# foc.net
KiCad netlist of a schematic drawn in Altium Designer
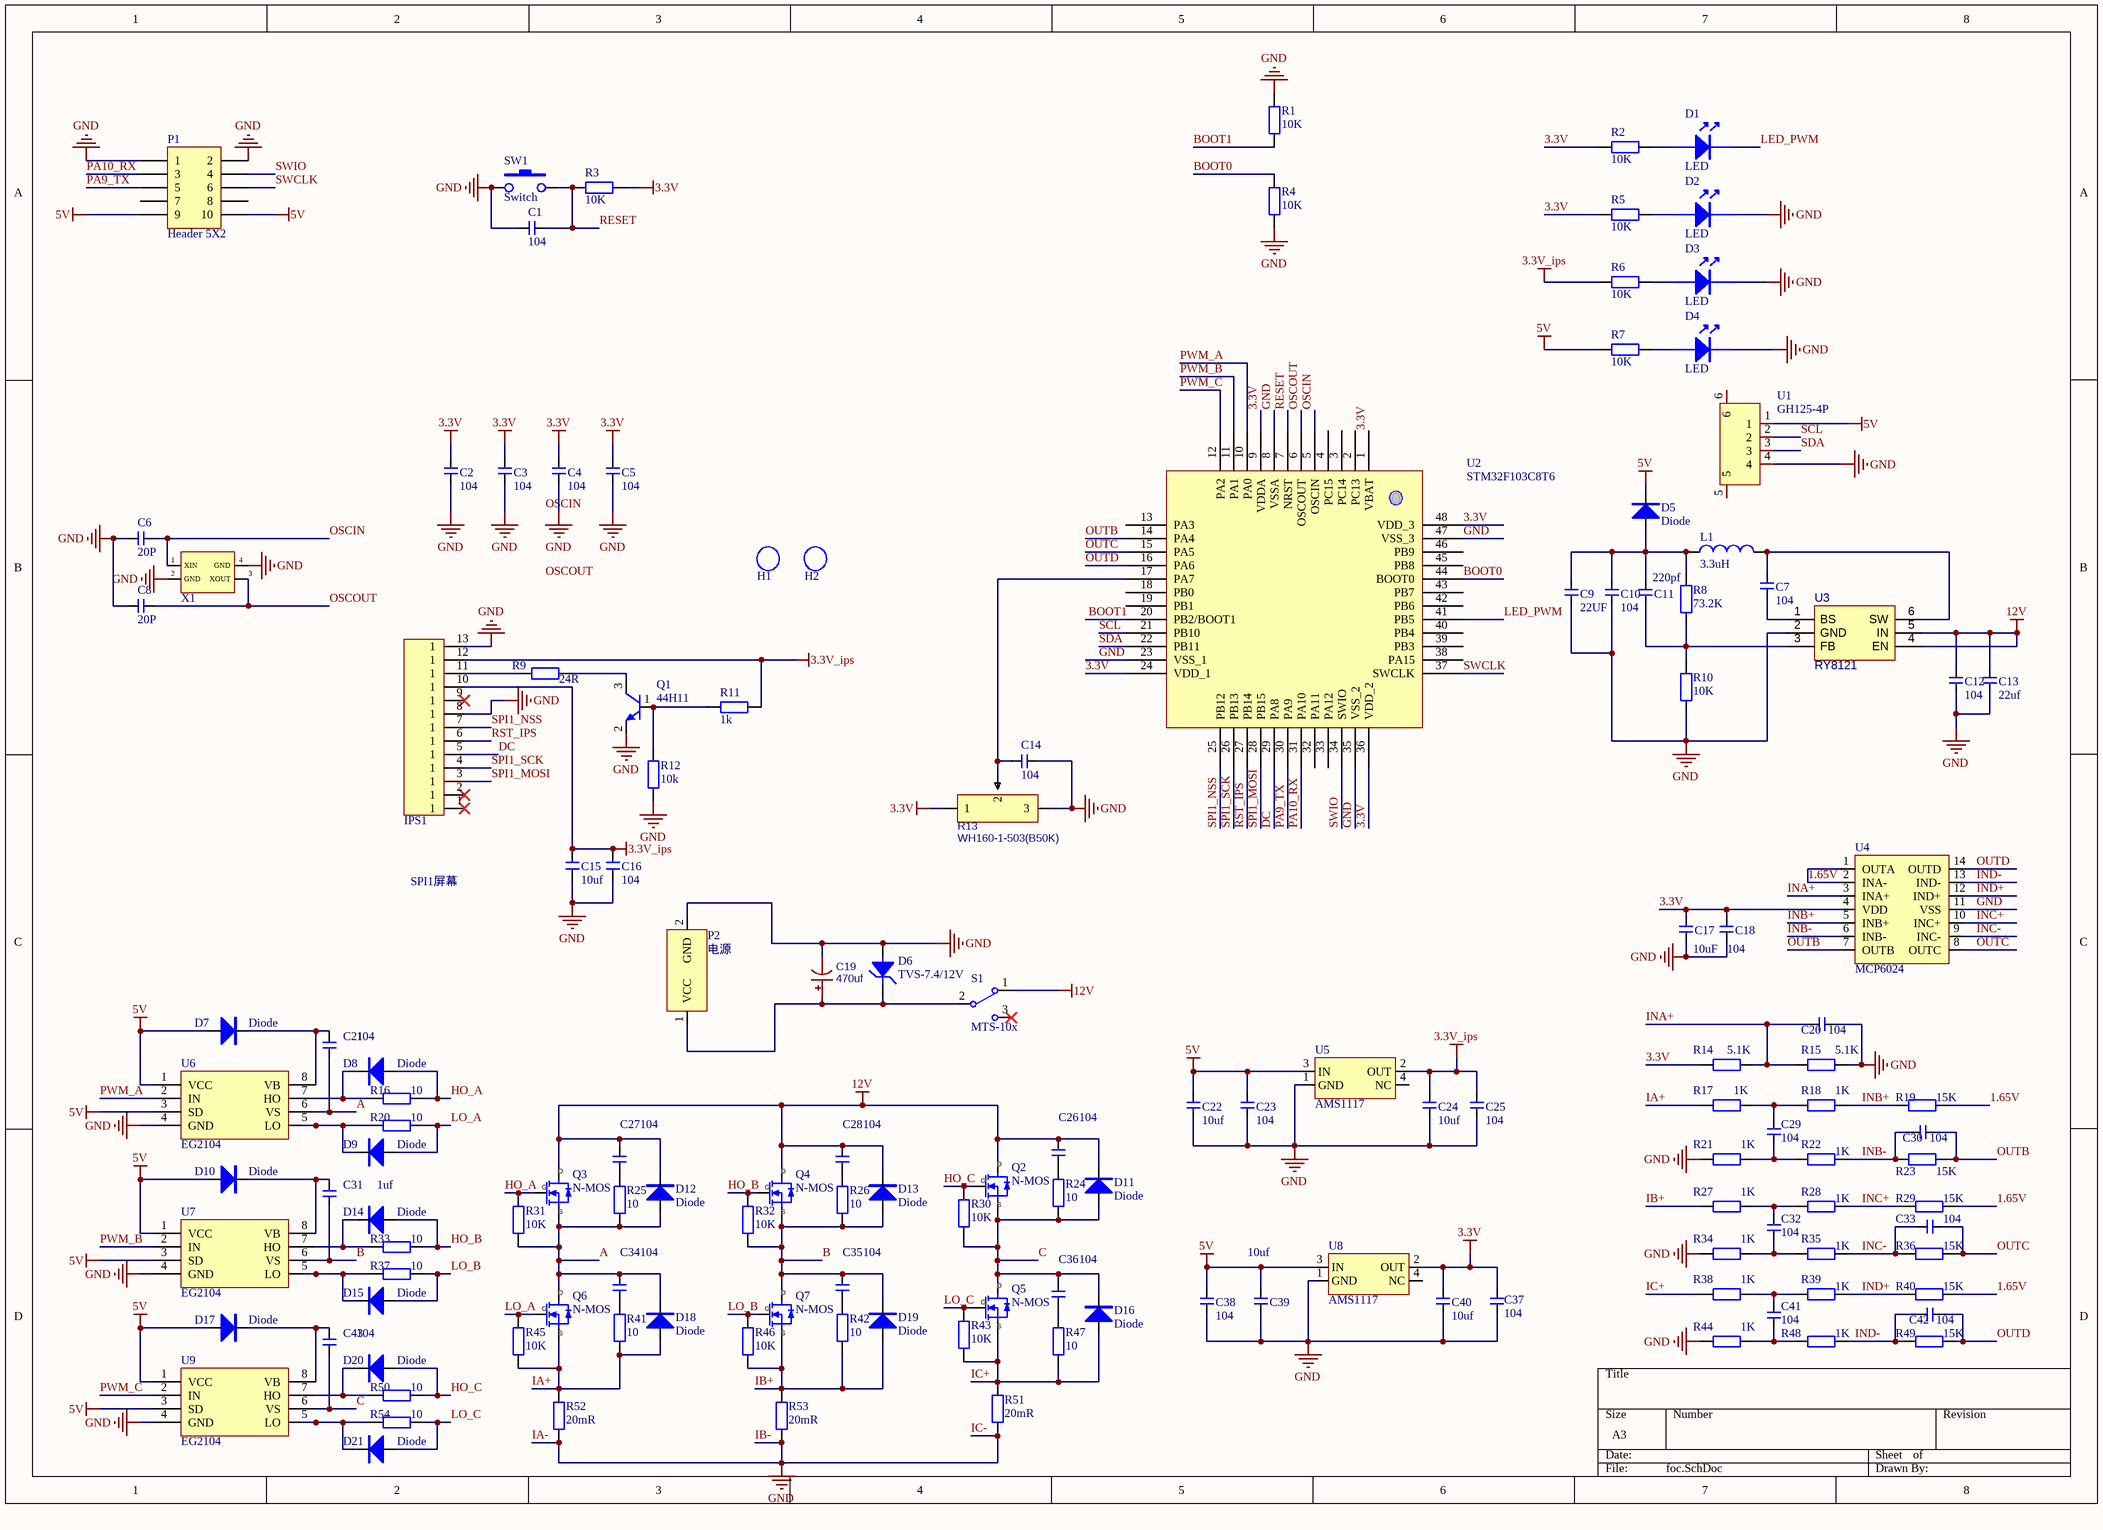
[diagram p0: foc.SchDoc]

(export (version "E")
  (design (tool "Eeschema 10.0.6"))
  (components
    (comp (ref "C1")
      (value "104")
      (footprint "C0603")
      (description "无极性电容")
      (fields (field (name "版权归属") "源创客"))
      (libsource (lib "鹏鹏总结的原理库") (part "C"))
    )
    (comp (ref "C2")
      (value "104")
      (footprint "C0603")
      (description "无极性电容")
      (fields (field (name "版权归属") "源创客"))
      (libsource (lib "鹏鹏总结的原理库") (part "C"))
    )
    (comp (ref "C3")
      (value "104")
      (footprint "C0603")
      (description "无极性电容")
      (fields (field (name "版权归属") "源创客"))
      (libsource (lib "鹏鹏总结的原理库") (part "C"))
    )
    (comp (ref "C4")
      (value "104")
      (footprint "C0603")
      (description "无极性电容")
      (fields (field (name "版权归属") "源创客"))
      (libsource (lib "鹏鹏总结的原理库") (part "C"))
    )
    (comp (ref "C5")
      (value "104")
      (footprint "C0603")
      (description "无极性电容")
      (fields (field (name "版权归属") "源创客"))
      (libsource (lib "鹏鹏总结的原理库") (part "C"))
    )
    (comp (ref "C6")
      (value "20P")
      (footprint "C0603")
      (description "无极性电容")
      (fields (field (name "版权归属") "源创客"))
      (libsource (lib "鹏鹏总结的原理库") (part "C"))
    )
    (comp (ref "C7")
      (value "104")
      (footprint "鹏鹏总结的pcb库:C0603")
      (description "无极性电容")
      (fields (field (name "版权归属") "源创客"))
      (libsource (lib "鹏鹏总结的原理库") (part "C"))
    )
    (comp (ref "C8")
      (value "20P")
      (footprint "C0603")
      (description "无极性电容")
      (fields (field (name "版权归属") "源创客"))
      (libsource (lib "鹏鹏总结的原理库") (part "C"))
    )
    (comp (ref "C9")
      (value "22UF")
      (footprint "鹏鹏总结的pcb库:C0603")
      (description "无极性电容")
      (fields (field (name "版权归属") "源创客"))
      (libsource (lib "鹏鹏总结的原理库") (part "C"))
    )
    (comp (ref "C10")
      (value "104")
      (footprint "鹏鹏总结的pcb库:C0603")
      (description "无极性电容")
      (fields (field (name "版权归属") "源创客"))
      (libsource (lib "鹏鹏总结的原理库") (part "C"))
    )
    (comp (ref "C11")
      (value "220pf")
      (footprint "鹏鹏总结的pcb库:C0603")
      (description "无极性电容")
      (fields (field (name "版权归属") "源创客"))
      (libsource (lib "鹏鹏总结的原理库") (part "C"))
    )
    (comp (ref "C12")
      (value "104")
      (footprint "鹏鹏总结的pcb库:C0603")
      (description "无极性电容")
      (fields (field (name "版权归属") "源创客"))
      (libsource (lib "鹏鹏总结的原理库") (part "C"))
    )
    (comp (ref "C13")
      (value "22uf")
      (footprint "鹏鹏总结的pcb库:C0603")
      (description "无极性电容")
      (fields (field (name "版权归属") "源创客"))
      (libsource (lib "鹏鹏总结的原理库") (part "C"))
    )
    (comp (ref "C14")
      (value "104")
      (footprint "C0603")
      (description "无极性电容")
      (fields (field (name "版权归属") "源创客"))
      (libsource (lib "鹏鹏总结的原理库") (part "C"))
    )
    (comp (ref "C15")
      (value "10uf")
      (footprint "鹏鹏总结的pcb库:C0603")
      (description "无极性电容")
      (fields (field (name "版权归属") "源创客"))
      (libsource (lib "") (part "C_1"))
    )
    (comp (ref "C16")
      (value "104")
      (footprint "鹏鹏总结的pcb库:C0603")
      (description "无极性电容")
      (fields (field (name "版权归属") "源创客"))
      (libsource (lib "") (part "C_1"))
    )
    (comp (ref "C17")
      (value "10uF")
      (footprint "鹏鹏总结的pcb库:C0603")
      (description "无极性电容")
      (fields (field (name "版权归属") "源创客"))
      (libsource (lib "鹏鹏总结的原理库") (part "C"))
    )
    (comp (ref "C18")
      (value "104")
      (footprint "鹏鹏总结的pcb库:C0603")
      (description "无极性电容")
      (fields (field (name "版权归属") "源创客"))
      (libsource (lib "鹏鹏总结的原理库") (part "C"))
    )
    (comp (ref "C19")
      (value "470uf")
      (footprint "CAP-SMD_BD6.3-L6.6-W6.6-LS7.2-R-RD")
      (description "电解电容 10uf  贴片型 钽电容的正极是实物有线的一段")
      (fields
        (field (name "BOM_MANUFACTURER PART") "RVT1V100M0405")
        (field (name "BOM_SUPPLIER PART") "C72485")
      )
      (libsource (lib "鹏鹏总结的原理库") (part "CAP+"))
    )
    (comp (ref "C20")
      (value "104")
      (footprint "鹏鹏总结的pcb库:C0603")
      (description "无极性电容")
      (fields (field (name "版权归属") "源创客"))
      (libsource (lib "鹏鹏总结的原理库") (part "C"))
    )
    (comp (ref "C21")
      (value "104")
      (footprint "鹏鹏总结的pcb库:C0603")
      (description "无极性电容")
      (fields (field (name "版权归属") "源创客"))
      (libsource (lib "鹏鹏总结的原理库") (part "C"))
    )
    (comp (ref "C22")
      (value "10uf")
      (footprint "鹏鹏总结的pcb库:C0603")
      (description "无极性电容")
      (fields (field (name "版权归属") "源创客"))
      (libsource (lib "鹏鹏总结的原理库") (part "C"))
    )
    (comp (ref "C23")
      (value "104")
      (footprint "鹏鹏总结的pcb库:C0603")
      (description "无极性电容")
      (fields (field (name "版权归属") "源创客"))
      (libsource (lib "鹏鹏总结的原理库") (part "C"))
    )
    (comp (ref "C24")
      (value "10uf")
      (footprint "鹏鹏总结的pcb库:C0603")
      (description "无极性电容")
      (fields (field (name "版权归属") "源创客"))
      (libsource (lib "鹏鹏总结的原理库") (part "C"))
    )
    (comp (ref "C25")
      (value "104")
      (footprint "鹏鹏总结的pcb库:C0603")
      (description "无极性电容")
      (fields (field (name "版权归属") "源创客"))
      (libsource (lib "鹏鹏总结的原理库") (part "C"))
    )
    (comp (ref "C26")
      (value "104")
      (footprint "鹏鹏总结的pcb库:C0603")
      (description "无极性电容")
      (fields (field (name "版权归属") "源创客"))
      (libsource (lib "鹏鹏总结的原理库") (part "C"))
    )
    (comp (ref "C27")
      (value "104")
      (footprint "鹏鹏总结的pcb库:C0603")
      (description "无极性电容")
      (fields (field (name "版权归属") "源创客"))
      (libsource (lib "鹏鹏总结的原理库") (part "C"))
    )
    (comp (ref "C28")
      (value "104")
      (footprint "鹏鹏总结的pcb库:C0603")
      (description "无极性电容")
      (fields (field (name "版权归属") "源创客"))
      (libsource (lib "鹏鹏总结的原理库") (part "C"))
    )
    (comp (ref "C29")
      (value "104")
      (footprint "鹏鹏总结的pcb库:C0603")
      (description "无极性电容")
      (fields (field (name "版权归属") "源创客"))
      (libsource (lib "鹏鹏总结的原理库") (part "C"))
    )
    (comp (ref "C30")
      (value "104")
      (footprint "鹏鹏总结的pcb库:C0603")
      (description "无极性电容")
      (fields (field (name "版权归属") "源创客"))
      (libsource (lib "鹏鹏总结的原理库") (part "C"))
    )
    (comp (ref "C31")
      (value "1uf")
      (footprint "鹏鹏总结的pcb库:C0603")
      (description "无极性电容")
      (fields (field (name "版权归属") "源创客"))
      (libsource (lib "鹏鹏总结的原理库") (part "C"))
    )
    (comp (ref "C32")
      (value "104")
      (footprint "鹏鹏总结的pcb库:C0603")
      (description "无极性电容")
      (fields (field (name "版权归属") "源创客"))
      (libsource (lib "鹏鹏总结的原理库") (part "C"))
    )
    (comp (ref "C33")
      (value "104")
      (footprint "鹏鹏总结的pcb库:C0603")
      (description "无极性电容")
      (fields (field (name "版权归属") "源创客"))
      (libsource (lib "鹏鹏总结的原理库") (part "C"))
    )
    (comp (ref "C34")
      (value "104")
      (footprint "鹏鹏总结的pcb库:C0603")
      (description "无极性电容")
      (fields (field (name "版权归属") "源创客"))
      (libsource (lib "鹏鹏总结的原理库") (part "C"))
    )
    (comp (ref "C35")
      (value "104")
      (footprint "鹏鹏总结的pcb库:C0603")
      (description "无极性电容")
      (fields (field (name "版权归属") "源创客"))
      (libsource (lib "鹏鹏总结的原理库") (part "C"))
    )
    (comp (ref "C36")
      (value "104")
      (footprint "鹏鹏总结的pcb库:C0603")
      (description "无极性电容")
      (fields (field (name "版权归属") "源创客"))
      (libsource (lib "鹏鹏总结的原理库") (part "C"))
    )
    (comp (ref "C37")
      (value "104")
      (footprint "鹏鹏总结的pcb库:C0603")
      (description "无极性电容")
      (fields (field (name "版权归属") "源创客"))
      (libsource (lib "鹏鹏总结的原理库") (part "C"))
    )
    (comp (ref "C38")
      (value "104")
      (footprint "鹏鹏总结的pcb库:C0603")
      (description "无极性电容")
      (fields (field (name "版权归属") "源创客"))
      (libsource (lib "鹏鹏总结的原理库") (part "C"))
    )
    (comp (ref "C39")
      (value "10uf")
      (footprint "鹏鹏总结的pcb库:C0603")
      (description "无极性电容")
      (fields (field (name "版权归属") "源创客"))
      (libsource (lib "鹏鹏总结的原理库") (part "C"))
    )
    (comp (ref "C40")
      (value "10uf")
      (footprint "鹏鹏总结的pcb库:C0603")
      (description "无极性电容")
      (fields (field (name "版权归属") "源创客"))
      (libsource (lib "鹏鹏总结的原理库") (part "C"))
    )
    (comp (ref "C41")
      (value "104")
      (footprint "鹏鹏总结的pcb库:C0603")
      (description "无极性电容")
      (fields (field (name "版权归属") "源创客"))
      (libsource (lib "鹏鹏总结的原理库") (part "C"))
    )
    (comp (ref "C42")
      (value "104")
      (footprint "鹏鹏总结的pcb库:C0603")
      (description "无极性电容")
      (fields (field (name "版权归属") "源创客"))
      (libsource (lib "鹏鹏总结的原理库") (part "C"))
    )
    (comp (ref "C43")
      (value "104")
      (footprint "鹏鹏总结的pcb库:C0603")
      (description "无极性电容")
      (fields (field (name "版权归属") "源创客"))
      (libsource (lib "鹏鹏总结的原理库") (part "C"))
    )
    (comp (ref "D1") (value "LED") (footprint "LED0603") (libsource (lib "鹏鹏总结的原理库") (part "LED")))
    (comp (ref "D2") (value "LED") (footprint "LED0603") (libsource (lib "鹏鹏总结的原理库") (part "LED")))
    (comp (ref "D3") (value "LED") (footprint "LED0603") (libsource (lib "鹏鹏总结的原理库") (part "LED")))
    (comp (ref "D4") (value "LED") (footprint "LED0603") (libsource (lib "鹏鹏总结的原理库") (part "LED")))
    (comp (ref "D5")
      (value "Diode")
      (footprint "SOD-123FL_L2.7-W1.8-LS3.8-RD")
      (description "Diode 1N series")
      (libsource (lib "鹏鹏总结的原理库") (part "二极管"))
    )
    (comp (ref "D6")
      (value "TVS-7.4/12V")
      (footprint "鹏鹏总结的pcb库:SMA")
      (libsource (lib "鹏鹏总结的原理库") (part "TVS-7.4/12V"))
    )
    (comp (ref "D7")
      (value "Diode")
      (footprint "SOD-123FL_L2.7-W1.8-LS3.8-RD")
      (description "Diode 1N series")
      (libsource (lib "鹏鹏总结的原理库") (part "二极管"))
    )
    (comp (ref "D8")
      (value "Diode")
      (footprint "ESC_L1.2-W0.8-LS1.6-RD")
      (description "Diode 1N series")
      (libsource (lib "鹏鹏总结的原理库") (part "二极管"))
    )
    (comp (ref "D9")
      (value "Diode")
      (footprint "ESC_L1.2-W0.8-LS1.6-RD")
      (description "Diode 1N series")
      (libsource (lib "鹏鹏总结的原理库") (part "二极管"))
    )
    (comp (ref "D10")
      (value "Diode")
      (footprint "SOD-123FL_L2.7-W1.8-LS3.8-RD")
      (description "Diode 1N series")
      (libsource (lib "鹏鹏总结的原理库") (part "二极管"))
    )
    (comp (ref "D11")
      (value "Diode")
      (footprint "SOD-123FL_L2.7-W1.8-LS3.8-RD")
      (description "Diode 1N series")
      (libsource (lib "鹏鹏总结的原理库") (part "二极管"))
    )
    (comp (ref "D12")
      (value "Diode")
      (footprint "SOD-123FL_L2.7-W1.8-LS3.8-RD")
      (description "Diode 1N series")
      (libsource (lib "鹏鹏总结的原理库") (part "二极管"))
    )
    (comp (ref "D13")
      (value "Diode")
      (footprint "SOD-123FL_L2.7-W1.8-LS3.8-RD")
      (description "Diode 1N series")
      (libsource (lib "鹏鹏总结的原理库") (part "二极管"))
    )
    (comp (ref "D14")
      (value "Diode")
      (footprint "ESC_L1.2-W0.8-LS1.6-RD")
      (description "Diode 1N series")
      (libsource (lib "鹏鹏总结的原理库") (part "二极管"))
    )
    (comp (ref "D15")
      (value "Diode")
      (footprint "ESC_L1.2-W0.8-LS1.6-RD")
      (description "Diode 1N series")
      (libsource (lib "鹏鹏总结的原理库") (part "二极管"))
    )
    (comp (ref "D16")
      (value "Diode")
      (footprint "SOD-123FL_L2.7-W1.8-LS3.8-RD")
      (description "Diode 1N series")
      (libsource (lib "鹏鹏总结的原理库") (part "二极管"))
    )
    (comp (ref "D17")
      (value "Diode")
      (footprint "SOD-123FL_L2.7-W1.8-LS3.8-RD")
      (description "Diode 1N series")
      (libsource (lib "鹏鹏总结的原理库") (part "二极管"))
    )
    (comp (ref "D18")
      (value "Diode")
      (footprint "SOD-123FL_L2.7-W1.8-LS3.8-RD")
      (description "Diode 1N series")
      (libsource (lib "鹏鹏总结的原理库") (part "二极管"))
    )
    (comp (ref "D19")
      (value "Diode")
      (footprint "SOD-123FL_L2.7-W1.8-LS3.8-RD")
      (description "Diode 1N series")
      (libsource (lib "鹏鹏总结的原理库") (part "二极管"))
    )
    (comp (ref "D20")
      (value "Diode")
      (footprint "ESC_L1.2-W0.8-LS1.6-RD")
      (description "Diode 1N series")
      (libsource (lib "鹏鹏总结的原理库") (part "二极管"))
    )
    (comp (ref "D21")
      (value "Diode")
      (footprint "ESC_L1.2-W0.8-LS1.6-RD")
      (description "Diode 1N series")
      (libsource (lib "鹏鹏总结的原理库") (part "二极管"))
    )
    (comp (ref "H1")
      (value "Hole")
      (footprint "铜柱孔3")
      (description "电机的洞")
      (libsource (lib "鹏鹏总结的原理库") (part "Hole"))
    )
    (comp (ref "H2")
      (value "Hole")
      (footprint "铜柱孔3")
      (description "电机的洞")
      (libsource (lib "鹏鹏总结的原理库") (part "Hole"))
    )
    (comp (ref "IPS1") (value "IPS1.14") (footprint "IPS") (libsource (lib "鹏鹏总结的原理库") (part "IPS1.14")))
    (comp (ref "L1")
      (value "3.3uH")
      (footprint "0402 TPC 4*4*2")
      (description "电感")
      (fields (field (name "版权归属") "源创客"))
      (libsource (lib "鹏鹏总结的原理库") (part "L"))
    )
    (comp (ref "P1")
      (value "Header 5X2")
      (footprint "HDR2X5")
      (description "Header, 5-Pin, Dual row")
      (fields (field (name "PUBLISHER") "Altium Limited"))
      (libsource (lib "Miscellaneous Connectors") (part "Header 5X2"))
    )
    (comp (ref "P2") (value "电源") (footprint "POWER") (libsource (lib "鹏鹏总结的原理库") (part "power")))
    (comp (ref "Q1")
      (value "44H11")
      (footprint "SOT-23-3_L2.9-W1.3-P1.90-LS2.4-BR")
      (description "NPN型")
      (fields (field (name "版权归属") "源创客"))
      (libsource (lib "鹏鹏总结的原理库") (part "NPN"))
    )
    (comp (ref "Q2")
      (value "N-MOS")
      (footprint "TDSON-8")
      (description "N沟场效应管")
      (fields (field (name "版权归属") "源创客"))
      (libsource (lib "鹏鹏总结的原理库") (part "N-MOS"))
    )
    (comp (ref "Q3")
      (value "N-MOS")
      (footprint "TDSON-8")
      (description "N沟场效应管")
      (fields (field (name "版权归属") "源创客"))
      (libsource (lib "鹏鹏总结的原理库") (part "N-MOS"))
    )
    (comp (ref "Q4")
      (value "N-MOS")
      (footprint "TDSON-8")
      (description "N沟场效应管")
      (fields (field (name "版权归属") "源创客"))
      (libsource (lib "鹏鹏总结的原理库") (part "N-MOS"))
    )
    (comp (ref "Q5")
      (value "N-MOS")
      (footprint "TDSON-8")
      (description "N沟场效应管")
      (fields (field (name "版权归属") "源创客"))
      (libsource (lib "鹏鹏总结的原理库") (part "N-MOS"))
    )
    (comp (ref "Q6")
      (value "N-MOS")
      (footprint "TDSON-8")
      (description "N沟场效应管")
      (fields (field (name "版权归属") "源创客"))
      (libsource (lib "鹏鹏总结的原理库") (part "N-MOS"))
    )
    (comp (ref "Q7")
      (value "N-MOS")
      (footprint "TDSON-8")
      (description "N沟场效应管")
      (fields (field (name "版权归属") "源创客"))
      (libsource (lib "鹏鹏总结的原理库") (part "N-MOS"))
    )
    (comp (ref "R1")
      (value "10K")
      (footprint "鹏鹏总结的pcb库:R0603")
      (description "电阻")
      (fields (field (name "版权归属") "源创客"))
      (libsource (lib "鹏鹏总结的原理库") (part "R"))
    )
    (comp (ref "R2")
      (value "10K")
      (footprint "鹏鹏总结的pcb库:R0603")
      (description "电阻")
      (fields (field (name "版权归属") "源创客"))
      (libsource (lib "鹏鹏总结的原理库") (part "R"))
    )
    (comp (ref "R3")
      (value "10K")
      (footprint "鹏鹏总结的pcb库:R0603")
      (description "电阻")
      (fields (field (name "版权归属") "源创客"))
      (libsource (lib "鹏鹏总结的原理库") (part "R"))
    )
    (comp (ref "R4")
      (value "10K")
      (footprint "鹏鹏总结的pcb库:R0603")
      (description "电阻")
      (fields (field (name "版权归属") "源创客"))
      (libsource (lib "鹏鹏总结的原理库") (part "R"))
    )
    (comp (ref "R5")
      (value "10K")
      (footprint "鹏鹏总结的pcb库:R0603")
      (description "电阻")
      (fields (field (name "版权归属") "源创客"))
      (libsource (lib "鹏鹏总结的原理库") (part "R"))
    )
    (comp (ref "R6")
      (value "10K")
      (footprint "鹏鹏总结的pcb库:R0603")
      (description "电阻")
      (fields (field (name "版权归属") "源创客"))
      (libsource (lib "鹏鹏总结的原理库") (part "R"))
    )
    (comp (ref "R7")
      (value "10K")
      (footprint "鹏鹏总结的pcb库:R0603")
      (description "电阻")
      (fields (field (name "版权归属") "源创客"))
      (libsource (lib "鹏鹏总结的原理库") (part "R"))
    )
    (comp (ref "R8")
      (value "73.2K")
      (footprint "鹏鹏总结的pcb库:R0603")
      (description "电阻")
      (fields (field (name "版权归属") "源创客"))
      (libsource (lib "鹏鹏总结的原理库") (part "R"))
    )
    (comp (ref "R9")
      (value "24R")
      (footprint "鹏鹏总结的pcb库:R0603")
      (description "电阻")
      (fields (field (name "版权归属") "源创客"))
      (libsource (lib "鹏鹏总结的原理库") (part "R"))
    )
    (comp (ref "R10")
      (value "10K")
      (footprint "鹏鹏总结的pcb库:R0603")
      (description "电阻")
      (fields (field (name "版权归属") "源创客"))
      (libsource (lib "鹏鹏总结的原理库") (part "R"))
    )
    (comp (ref "R11")
      (value "1k")
      (footprint "鹏鹏总结的pcb库:R0603")
      (description "电阻")
      (fields (field (name "版权归属") "源创客"))
      (libsource (lib "鹏鹏总结的原理库") (part "R"))
    )
    (comp (ref "R12")
      (value "10k")
      (footprint "鹏鹏总结的pcb库:R0603")
      (description "电阻")
      (fields (field (name "版权归属") "源创客"))
      (libsource (lib "鹏鹏总结的原理库") (part "R"))
    )
    (comp (ref "R13")
      (value "WH160-1-503(B50K)")
      (footprint "滑动变阻器")
      (description "拨码开关")
      (fields (field (name "MANUFACTURER") "JML"))
      (libsource (lib "鹏鹏总结的原理库") (part "WH160-1-503(B50K)"))
    )
    (comp (ref "R14")
      (value "5.1K")
      (footprint "鹏鹏总结的pcb库:R0603")
      (description "电阻")
      (fields (field (name "版权归属") "源创客"))
      (libsource (lib "鹏鹏总结的原理库") (part "R"))
    )
    (comp (ref "R15")
      (value "5.1K")
      (footprint "鹏鹏总结的pcb库:R0603")
      (description "电阻")
      (fields (field (name "版权归属") "源创客"))
      (libsource (lib "鹏鹏总结的原理库") (part "R"))
    )
    (comp (ref "R16")
      (value "10")
      (footprint "鹏鹏总结的pcb库:R0603")
      (description "电阻")
      (fields (field (name "版权归属") "源创客"))
      (libsource (lib "鹏鹏总结的原理库") (part "R"))
    )
    (comp (ref "R17")
      (value "1K")
      (footprint "鹏鹏总结的pcb库:R0603")
      (description "电阻")
      (fields (field (name "版权归属") "源创客"))
      (libsource (lib "鹏鹏总结的原理库") (part "R"))
    )
    (comp (ref "R18")
      (value "1K")
      (footprint "鹏鹏总结的pcb库:R0603")
      (description "电阻")
      (fields (field (name "版权归属") "源创客"))
      (libsource (lib "鹏鹏总结的原理库") (part "R"))
    )
    (comp (ref "R19")
      (value "15K")
      (footprint "鹏鹏总结的pcb库:R0603")
      (description "电阻")
      (fields (field (name "版权归属") "源创客"))
      (libsource (lib "鹏鹏总结的原理库") (part "R"))
    )
    (comp (ref "R20")
      (value "10")
      (footprint "鹏鹏总结的pcb库:R0603")
      (description "电阻")
      (fields (field (name "版权归属") "源创客"))
      (libsource (lib "鹏鹏总结的原理库") (part "R"))
    )
    (comp (ref "R21")
      (value "1K")
      (footprint "鹏鹏总结的pcb库:R0603")
      (description "电阻")
      (fields (field (name "版权归属") "源创客"))
      (libsource (lib "鹏鹏总结的原理库") (part "R"))
    )
    (comp (ref "R22")
      (value "1K")
      (footprint "鹏鹏总结的pcb库:R0603")
      (description "电阻")
      (fields (field (name "版权归属") "源创客"))
      (libsource (lib "鹏鹏总结的原理库") (part "R"))
    )
    (comp (ref "R23")
      (value "15K")
      (footprint "鹏鹏总结的pcb库:R0603")
      (description "电阻")
      (fields (field (name "版权归属") "源创客"))
      (libsource (lib "鹏鹏总结的原理库") (part "R"))
    )
    (comp (ref "R24")
      (value "10")
      (footprint "鹏鹏总结的pcb库:R0603")
      (description "电阻")
      (fields (field (name "版权归属") "源创客"))
      (libsource (lib "鹏鹏总结的原理库") (part "R"))
    )
    (comp (ref "R25")
      (value "10")
      (footprint "鹏鹏总结的pcb库:R0603")
      (description "电阻")
      (fields (field (name "版权归属") "源创客"))
      (libsource (lib "鹏鹏总结的原理库") (part "R"))
    )
    (comp (ref "R26")
      (value "10")
      (footprint "鹏鹏总结的pcb库:R0603")
      (description "电阻")
      (fields (field (name "版权归属") "源创客"))
      (libsource (lib "鹏鹏总结的原理库") (part "R"))
    )
    (comp (ref "R27")
      (value "1K")
      (footprint "鹏鹏总结的pcb库:R0603")
      (description "电阻")
      (fields (field (name "版权归属") "源创客"))
      (libsource (lib "鹏鹏总结的原理库") (part "R"))
    )
    (comp (ref "R28")
      (value "1K")
      (footprint "鹏鹏总结的pcb库:R0603")
      (description "电阻")
      (fields (field (name "版权归属") "源创客"))
      (libsource (lib "鹏鹏总结的原理库") (part "R"))
    )
    (comp (ref "R29")
      (value "15K")
      (footprint "鹏鹏总结的pcb库:R0603")
      (description "电阻")
      (fields (field (name "版权归属") "源创客"))
      (libsource (lib "鹏鹏总结的原理库") (part "R"))
    )
    (comp (ref "R30")
      (value "10K")
      (footprint "鹏鹏总结的pcb库:R0603")
      (description "电阻")
      (fields (field (name "版权归属") "源创客"))
      (libsource (lib "鹏鹏总结的原理库") (part "R"))
    )
    (comp (ref "R31")
      (value "10K")
      (footprint "鹏鹏总结的pcb库:R0603")
      (description "电阻")
      (fields (field (name "版权归属") "源创客"))
      (libsource (lib "鹏鹏总结的原理库") (part "R"))
    )
    (comp (ref "R32")
      (value "10K")
      (footprint "鹏鹏总结的pcb库:R0603")
      (description "电阻")
      (fields (field (name "版权归属") "源创客"))
      (libsource (lib "鹏鹏总结的原理库") (part "R"))
    )
    (comp (ref "R33")
      (value "10")
      (footprint "鹏鹏总结的pcb库:R0603")
      (description "电阻")
      (fields (field (name "版权归属") "源创客"))
      (libsource (lib "鹏鹏总结的原理库") (part "R"))
    )
    (comp (ref "R34")
      (value "1K")
      (footprint "鹏鹏总结的pcb库:R0603")
      (description "电阻")
      (fields (field (name "版权归属") "源创客"))
      (libsource (lib "鹏鹏总结的原理库") (part "R"))
    )
    (comp (ref "R35")
      (value "1K")
      (footprint "鹏鹏总结的pcb库:R0603")
      (description "电阻")
      (fields (field (name "版权归属") "源创客"))
      (libsource (lib "鹏鹏总结的原理库") (part "R"))
    )
    (comp (ref "R36")
      (value "15K")
      (footprint "鹏鹏总结的pcb库:R0603")
      (description "电阻")
      (fields (field (name "版权归属") "源创客"))
      (libsource (lib "鹏鹏总结的原理库") (part "R"))
    )
    (comp (ref "R37")
      (value "10")
      (footprint "鹏鹏总结的pcb库:R0603")
      (description "电阻")
      (fields (field (name "版权归属") "源创客"))
      (libsource (lib "鹏鹏总结的原理库") (part "R"))
    )
    (comp (ref "R38")
      (value "1K")
      (footprint "鹏鹏总结的pcb库:R0603")
      (description "电阻")
      (fields (field (name "版权归属") "源创客"))
      (libsource (lib "鹏鹏总结的原理库") (part "R"))
    )
    (comp (ref "R39")
      (value "1K")
      (footprint "鹏鹏总结的pcb库:R0603")
      (description "电阻")
      (fields (field (name "版权归属") "源创客"))
      (libsource (lib "鹏鹏总结的原理库") (part "R"))
    )
    (comp (ref "R40")
      (value "15K")
      (footprint "鹏鹏总结的pcb库:R0603")
      (description "电阻")
      (fields (field (name "版权归属") "源创客"))
      (libsource (lib "鹏鹏总结的原理库") (part "R"))
    )
    (comp (ref "R41")
      (value "10")
      (footprint "鹏鹏总结的pcb库:R0603")
      (description "电阻")
      (fields (field (name "版权归属") "源创客"))
      (libsource (lib "鹏鹏总结的原理库") (part "R"))
    )
    (comp (ref "R42")
      (value "10")
      (footprint "鹏鹏总结的pcb库:R0603")
      (description "电阻")
      (fields (field (name "版权归属") "源创客"))
      (libsource (lib "鹏鹏总结的原理库") (part "R"))
    )
    (comp (ref "R43")
      (value "10K")
      (footprint "鹏鹏总结的pcb库:R0603")
      (description "电阻")
      (fields (field (name "版权归属") "源创客"))
      (libsource (lib "鹏鹏总结的原理库") (part "R"))
    )
    (comp (ref "R44")
      (value "1K")
      (footprint "鹏鹏总结的pcb库:R0603")
      (description "电阻")
      (fields (field (name "版权归属") "源创客"))
      (libsource (lib "鹏鹏总结的原理库") (part "R"))
    )
    (comp (ref "R45")
      (value "10K")
      (footprint "鹏鹏总结的pcb库:R0603")
      (description "电阻")
      (fields (field (name "版权归属") "源创客"))
      (libsource (lib "鹏鹏总结的原理库") (part "R"))
    )
    (comp (ref "R46")
      (value "10K")
      (footprint "鹏鹏总结的pcb库:R0603")
      (description "电阻")
      (fields (field (name "版权归属") "源创客"))
      (libsource (lib "鹏鹏总结的原理库") (part "R"))
    )
    (comp (ref "R47")
      (value "10")
      (footprint "鹏鹏总结的pcb库:R0603")
      (description "电阻")
      (fields (field (name "版权归属") "源创客"))
      (libsource (lib "鹏鹏总结的原理库") (part "R"))
    )
    (comp (ref "R48")
      (value "1K")
      (footprint "鹏鹏总结的pcb库:R0603")
      (description "电阻")
      (fields (field (name "版权归属") "源创客"))
      (libsource (lib "鹏鹏总结的原理库") (part "R"))
    )
    (comp (ref "R49")
      (value "15K")
      (footprint "鹏鹏总结的pcb库:R0603")
      (description "电阻")
      (fields (field (name "版权归属") "源创客"))
      (libsource (lib "鹏鹏总结的原理库") (part "R"))
    )
    (comp (ref "R50")
      (value "10")
      (footprint "鹏鹏总结的pcb库:R0603")
      (description "电阻")
      (fields (field (name "版权归属") "源创客"))
      (libsource (lib "鹏鹏总结的原理库") (part "R"))
    )
    (comp (ref "R51")
      (value "20mR")
      (footprint "R1206")
      (description "电阻")
      (fields (field (name "版权归属") "源创客"))
      (libsource (lib "鹏鹏总结的原理库") (part "R"))
    )
    (comp (ref "R52")
      (value "20mR")
      (footprint "R1206")
      (description "电阻")
      (fields (field (name "版权归属") "源创客"))
      (libsource (lib "鹏鹏总结的原理库") (part "R"))
    )
    (comp (ref "R53")
      (value "20mR")
      (footprint "R1206")
      (description "电阻")
      (fields (field (name "版权归属") "源创客"))
      (libsource (lib "鹏鹏总结的原理库") (part "R"))
    )
    (comp (ref "R54")
      (value "10")
      (footprint "鹏鹏总结的pcb库:R0603")
      (description "电阻")
      (fields (field (name "版权归属") "源创客"))
      (libsource (lib "鹏鹏总结的原理库") (part "R"))
    )
    (comp (ref "S1")
      (value "MTS-10x")
      (footprint "SW-TH_HOOYA_SS-12D10G4")
      (description "MTS10x系列3脚扭子开关")
      (fields (field (name "版权归属") "源创客"))
      (libsource (lib "鹏鹏总结的原理库") (part "MTS-10x"))
    )
    (comp (ref "SW1")
      (value "Switch")
      (footprint "SW-SMD_L4.0-W2.9-LS5.0")
      (description "SWITCH")
      (libsource (lib "鹏鹏总结的原理库") (part "Switch"))
    )
    (comp (ref "U1")
      (value "GH125-4P")
      (footprint "CONN-SMD_4P-P1.27_GH125-S04DCA-00")
      (libsource (lib "鹏鹏总结的原理库") (part "GH125-4P"))
    )
    (comp (ref "U2")
      (value "STM32F103C8T6")
      (footprint "48P")
      (libsource (lib "STM32F103C8T6") (part "STM32F103C8T6"))
    )
    (comp (ref "U3")
      (value "RY8121")
      (footprint "SOT-23-6")
      (description "18V 2A 1MHz Synchronous Step-Down Regulator")
      (libsource (lib "鹏鹏总结的原理库") (part "RY8121"))
    )
    (comp (ref "U4") (value "MCP6024") (footprint "SOP14_L") (libsource (lib "鹏鹏总结的原理库") (part "MCP6024")))
    (comp (ref "U5")
      (value "AMS1117")
      (footprint "SOT-89_L4.5-W2.5-P1.50-LS4.2-BR")
      (libsource (lib "鹏鹏总结的原理库") (part "AMS1117"))
    )
    (comp (ref "U6") (value "EG2104") (footprint "SOP-8") (libsource (lib "鹏鹏总结的原理库") (part "EG2104")))
    (comp (ref "U7") (value "EG2104") (footprint "SOP-8") (libsource (lib "鹏鹏总结的原理库") (part "EG2104")))
    (comp (ref "U8")
      (value "AMS1117")
      (footprint "SOT-89_L4.5-W2.5-P1.50-LS4.2-BR")
      (libsource (lib "鹏鹏总结的原理库") (part "AMS1117"))
    )
    (comp (ref "U9") (value "EG2104") (footprint "SOP-8") (libsource (lib "鹏鹏总结的原理库") (part "EG2104")))
    (comp (ref "X1")
      (value "XTAL-4")
      (footprint "OSC-SMD_4P-L3.2-W2.5-BL")
      (description "贴片晶振")
      (libsource (lib "鹏鹏总结的原理库") (part "XTAL-4"))
    )
  )
  (nets
    (net (code "1") (name "/1.65V") (class "Default")
      (node (ref "R19") (pin "1") (pinfunction "1_1") (pintype "passive"))
      (node (ref "R29") (pin "1") (pinfunction "1_1") (pintype "passive"))
      (node (ref "R40") (pin "1") (pinfunction "1_1") (pintype "passive"))
      (node (ref "U4") (pin "1") (pinfunction "OUTA_1") (pintype "passive"))
      (node (ref "U4") (pin "2") (pinfunction "INA-_2") (pintype "passive"))
    )
    (net (code "2") (name "/A") (class "Default")
      (node (ref "C21") (pin "1") (pinfunction "1_1") (pintype "passive"))
      (node (ref "C34") (pin "2") (pinfunction "2_2") (pintype "passive"))
      (node (ref "D12") (pin "2") (pintype "passive"))
      (node (ref "D18") (pin "1") (pintype "passive"))
      (node (ref "Q3") (pin "3") (pinfunction "S_3") (pintype "passive"))
      (node (ref "Q6") (pin "1") (pinfunction "D_1") (pintype "passive"))
      (node (ref "R25") (pin "2") (pinfunction "2_2") (pintype "passive"))
      (node (ref "R31") (pin "1") (pinfunction "1_1") (pintype "passive"))
      (node (ref "U6") (pin "6") (pinfunction "VS_6") (pintype "passive"))
    )
    (net (code "3") (name "/B") (class "Default")
      (node (ref "C31") (pin "1") (pinfunction "1_1") (pintype "passive"))
      (node (ref "C35") (pin "2") (pinfunction "2_2") (pintype "passive"))
      (node (ref "D13") (pin "2") (pintype "passive"))
      (node (ref "D19") (pin "1") (pintype "passive"))
      (node (ref "Q4") (pin "3") (pinfunction "S_3") (pintype "passive"))
      (node (ref "Q7") (pin "1") (pinfunction "D_1") (pintype "passive"))
      (node (ref "R26") (pin "2") (pinfunction "2_2") (pintype "passive"))
      (node (ref "R32") (pin "1") (pinfunction "1_1") (pintype "passive"))
      (node (ref "U7") (pin "6") (pinfunction "VS_6") (pintype "passive"))
    )
    (net (code "4") (name "/BOOT0") (class "Default")
      (node (ref "R4") (pin "1") (pinfunction "1_1") (pintype "passive"))
      (node (ref "U2") (pin "44") (pinfunction "BOOT0_44") (pintype "passive"))
    )
    (net (code "5") (name "/BOOT1") (class "Default")
      (node (ref "R1") (pin "2") (pinfunction "2_2") (pintype "passive"))
      (node (ref "U2") (pin "20") (pinfunction "PB2/BOOT1_20") (pintype "passive"))
    )
    (net (code "6") (name "/C") (class "Default")
      (node (ref "C36") (pin "2") (pinfunction "2_2") (pintype "passive"))
      (node (ref "C43") (pin "1") (pinfunction "1_1") (pintype "passive"))
      (node (ref "D11") (pin "2") (pintype "passive"))
      (node (ref "D16") (pin "1") (pintype "passive"))
      (node (ref "Q2") (pin "3") (pinfunction "S_3") (pintype "passive"))
      (node (ref "Q5") (pin "1") (pinfunction "D_1") (pintype "passive"))
      (node (ref "R24") (pin "2") (pinfunction "2_2") (pintype "passive"))
      (node (ref "R30") (pin "1") (pinfunction "1_1") (pintype "passive"))
      (node (ref "U9") (pin "6") (pinfunction "VS_6") (pintype "passive"))
    )
    (net (code "7") (name "/DC") (class "Default")
      (node (ref "IPS1") (pin "5") (pinfunction "1_5") (pintype "passive"))
      (node (ref "U2") (pin "29") (pinfunction "PA8_29") (pintype "passive"))
    )
    (net (code "8") (name "/HO_A") (class "Default")
      (node (ref "D8") (pin "2") (pintype "passive"))
      (node (ref "Q3") (pin "2") (pinfunction "G_2") (pintype "passive"))
      (node (ref "R16") (pin "1") (pinfunction "1_1") (pintype "passive"))
      (node (ref "R31") (pin "2") (pinfunction "2_2") (pintype "passive"))
    )
    (net (code "9") (name "/HO_B") (class "Default")
      (node (ref "D14") (pin "2") (pintype "passive"))
      (node (ref "Q4") (pin "2") (pinfunction "G_2") (pintype "passive"))
      (node (ref "R32") (pin "2") (pinfunction "2_2") (pintype "passive"))
      (node (ref "R33") (pin "1") (pinfunction "1_1") (pintype "passive"))
    )
    (net (code "10") (name "/HO_C") (class "Default")
      (node (ref "D20") (pin "2") (pintype "passive"))
      (node (ref "Q2") (pin "2") (pinfunction "G_2") (pintype "passive"))
      (node (ref "R30") (pin "2") (pinfunction "2_2") (pintype "passive"))
      (node (ref "R50") (pin "1") (pinfunction "1_1") (pintype "passive"))
    )
    (net (code "11") (name "/IA+") (class "Default")
      (node (ref "D18") (pin "2") (pintype "passive"))
      (node (ref "Q6") (pin "3") (pinfunction "S_3") (pintype "passive"))
      (node (ref "R17") (pin "2") (pinfunction "2_2") (pintype "passive"))
      (node (ref "R41") (pin "2") (pinfunction "2_2") (pintype "passive"))
      (node (ref "R45") (pin "1") (pinfunction "1_1") (pintype "passive"))
      (node (ref "R52") (pin "2") (pinfunction "2_2") (pintype "passive"))
    )
    (net (code "12") (name "/IB+") (class "Default")
      (node (ref "D19") (pin "2") (pintype "passive"))
      (node (ref "Q7") (pin "3") (pinfunction "S_3") (pintype "passive"))
      (node (ref "R27") (pin "2") (pinfunction "2_2") (pintype "passive"))
      (node (ref "R42") (pin "2") (pinfunction "2_2") (pintype "passive"))
      (node (ref "R46") (pin "1") (pinfunction "1_1") (pintype "passive"))
      (node (ref "R53") (pin "2") (pinfunction "2_2") (pintype "passive"))
    )
    (net (code "13") (name "/IC+") (class "Default")
      (node (ref "D16") (pin "2") (pintype "passive"))
      (node (ref "Q5") (pin "3") (pinfunction "S_3") (pintype "passive"))
      (node (ref "R38") (pin "2") (pinfunction "2_2") (pintype "passive"))
      (node (ref "R43") (pin "1") (pinfunction "1_1") (pintype "passive"))
      (node (ref "R47") (pin "2") (pinfunction "2_2") (pintype "passive"))
      (node (ref "R51") (pin "2") (pinfunction "2_2") (pintype "passive"))
    )
    (net (code "14") (name "/INA+") (class "Default")
      (node (ref "C20") (pin "2") (pinfunction "2_2") (pintype "passive"))
      (node (ref "R14") (pin "1") (pinfunction "1_1") (pintype "passive"))
      (node (ref "R15") (pin "2") (pinfunction "2_2") (pintype "passive"))
      (node (ref "U4") (pin "3") (pinfunction "INA+_3") (pintype "passive"))
    )
    (net (code "15") (name "/INB+") (class "Default")
      (node (ref "R18") (pin "1") (pinfunction "1_1") (pintype "passive"))
      (node (ref "R19") (pin "2") (pinfunction "2_2") (pintype "passive"))
      (node (ref "U4") (pin "5") (pinfunction "INB+_5") (pintype "passive"))
    )
    (net (code "16") (name "/INB-") (class "Default")
      (node (ref "C30") (pin "2") (pinfunction "2_2") (pintype "passive"))
      (node (ref "R22") (pin "1") (pinfunction "1_1") (pintype "passive"))
      (node (ref "R23") (pin "2") (pinfunction "2_2") (pintype "passive"))
      (node (ref "U4") (pin "6") (pinfunction "INB-_6") (pintype "passive"))
    )
    (net (code "17") (name "/INC+") (class "Default")
      (node (ref "R28") (pin "1") (pinfunction "1_1") (pintype "passive"))
      (node (ref "R29") (pin "2") (pinfunction "2_2") (pintype "passive"))
      (node (ref "U4") (pin "10") (pinfunction "INC+_10") (pintype "passive"))
    )
    (net (code "18") (name "/INC-") (class "Default")
      (node (ref "C33") (pin "2") (pinfunction "2_2") (pintype "passive"))
      (node (ref "R35") (pin "1") (pinfunction "1_1") (pintype "passive"))
      (node (ref "R36") (pin "2") (pinfunction "2_2") (pintype "passive"))
      (node (ref "U4") (pin "9") (pinfunction "INC-_9") (pintype "passive"))
    )
    (net (code "19") (name "/IND+") (class "Default")
      (node (ref "R39") (pin "1") (pinfunction "1_1") (pintype "passive"))
      (node (ref "R40") (pin "2") (pinfunction "2_2") (pintype "passive"))
      (node (ref "U4") (pin "12") (pinfunction "IND+_12") (pintype "passive"))
    )
    (net (code "20") (name "/IND-") (class "Default")
      (node (ref "C42") (pin "2") (pinfunction "2_2") (pintype "passive"))
      (node (ref "R48") (pin "1") (pinfunction "1_1") (pintype "passive"))
      (node (ref "R49") (pin "2") (pinfunction "2_2") (pintype "passive"))
      (node (ref "U4") (pin "13") (pinfunction "IND-_13") (pintype "passive"))
    )
    (net (code "21") (name "/LED_PWM") (class "Default")
      (node (ref "D1") (pin "N") (pinfunction "2_N") (pintype "passive"))
      (node (ref "U2") (pin "41") (pinfunction "PB5_41") (pintype "passive"))
    )
    (net (code "22") (name "/LO_A") (class "Default")
      (node (ref "D9") (pin "2") (pintype "passive"))
      (node (ref "Q6") (pin "2") (pinfunction "G_2") (pintype "passive"))
      (node (ref "R20") (pin "1") (pinfunction "1_1") (pintype "passive"))
      (node (ref "R45") (pin "2") (pinfunction "2_2") (pintype "passive"))
    )
    (net (code "23") (name "/LO_B") (class "Default")
      (node (ref "D15") (pin "2") (pintype "passive"))
      (node (ref "Q7") (pin "2") (pinfunction "G_2") (pintype "passive"))
      (node (ref "R37") (pin "1") (pinfunction "1_1") (pintype "passive"))
      (node (ref "R46") (pin "2") (pinfunction "2_2") (pintype "passive"))
    )
    (net (code "24") (name "/LO_C") (class "Default")
      (node (ref "D21") (pin "2") (pintype "passive"))
      (node (ref "Q5") (pin "2") (pinfunction "G_2") (pintype "passive"))
      (node (ref "R43") (pin "2") (pinfunction "2_2") (pintype "passive"))
      (node (ref "R54") (pin "1") (pinfunction "1_1") (pintype "passive"))
    )
    (net (code "25") (name "/OSCIN") (class "Default")
      (node (ref "C6") (pin "1") (pinfunction "1_1") (pintype "passive"))
      (node (ref "U2") (pin "5") (pinfunction "OSCIN_5") (pintype "passive"))
      (node (ref "X1") (pin "1") (pinfunction "XIN_1") (pintype "passive"))
    )
    (net (code "26") (name "/OSCOUT") (class "Default")
      (node (ref "C8") (pin "1") (pinfunction "1_1") (pintype "passive"))
      (node (ref "U2") (pin "6") (pinfunction "OSCOUT_6") (pintype "passive"))
      (node (ref "X1") (pin "3") (pinfunction "XOUT_3") (pintype "passive"))
    )
    (net (code "27") (name "/OUTB") (class "Default")
      (node (ref "C30") (pin "1") (pinfunction "1_1") (pintype "passive"))
      (node (ref "R23") (pin "1") (pinfunction "1_1") (pintype "passive"))
      (node (ref "U2") (pin "14") (pinfunction "PA4_14") (pintype "passive"))
      (node (ref "U4") (pin "7") (pinfunction "OUTB_7") (pintype "passive"))
    )
    (net (code "28") (name "/OUTC") (class "Default")
      (node (ref "C33") (pin "1") (pinfunction "1_1") (pintype "passive"))
      (node (ref "R36") (pin "1") (pinfunction "1_1") (pintype "passive"))
      (node (ref "U2") (pin "15") (pinfunction "PA5_15") (pintype "passive"))
      (node (ref "U4") (pin "8") (pinfunction "OUTC_8") (pintype "passive"))
    )
    (net (code "29") (name "/OUTD") (class "Default")
      (node (ref "C42") (pin "1") (pinfunction "1_1") (pintype "passive"))
      (node (ref "R49") (pin "1") (pinfunction "1_1") (pintype "passive"))
      (node (ref "U2") (pin "16") (pinfunction "PA6_16") (pintype "passive"))
      (node (ref "U4") (pin "14") (pinfunction "OUTD_14") (pintype "passive"))
    )
    (net (code "30") (name "/PA9_TX") (class "Default")
      (node (ref "P1") (pin "5") (pinfunction "5_5") (pintype "passive"))
      (node (ref "U2") (pin "30") (pinfunction "PA9_30") (pintype "passive"))
    )
    (net (code "31") (name "/PA10_RX") (class "Default")
      (node (ref "P1") (pin "3") (pinfunction "3_3") (pintype "passive"))
      (node (ref "U2") (pin "31") (pinfunction "PA10_31") (pintype "passive"))
    )
    (net (code "32") (name "/PWM_A") (class "Default")
      (node (ref "U2") (pin "10") (pinfunction "PA0_10") (pintype "passive"))
      (node (ref "U6") (pin "2") (pinfunction "IN_2") (pintype "passive"))
    )
    (net (code "33") (name "/PWM_B") (class "Default")
      (node (ref "U2") (pin "11") (pinfunction "PA1_11") (pintype "passive"))
      (node (ref "U7") (pin "2") (pinfunction "IN_2") (pintype "passive"))
    )
    (net (code "34") (name "/PWM_C") (class "Default")
      (node (ref "U2") (pin "12") (pinfunction "PA2_12") (pintype "passive"))
      (node (ref "U9") (pin "2") (pinfunction "IN_2") (pintype "passive"))
    )
    (net (code "35") (name "/RESET") (class "Default")
      (node (ref "C1") (pin "1") (pinfunction "1_1") (pintype "passive"))
      (node (ref "R3") (pin "2") (pinfunction "2_2") (pintype "passive"))
      (node (ref "SW1") (pin "2") (pinfunction "2_2") (pintype "passive"))
      (node (ref "U2") (pin "7") (pinfunction "NRST_7") (pintype "passive"))
    )
    (net (code "36") (name "/RST_IPS") (class "Default")
      (node (ref "IPS1") (pin "6") (pinfunction "1_6") (pintype "passive"))
      (node (ref "U2") (pin "27") (pinfunction "PB14_27") (pintype "passive"))
    )
    (net (code "37") (name "/SCL") (class "Default")
      (node (ref "U1") (pin "2") (pinfunction "2_2") (pintype "passive"))
      (node (ref "U2") (pin "21") (pinfunction "PB10_21") (pintype "passive"))
    )
    (net (code "38") (name "/SDA") (class "Default")
      (node (ref "U1") (pin "3") (pinfunction "3_3") (pintype "passive"))
      (node (ref "U2") (pin "22") (pinfunction "PB11_22") (pintype "passive"))
    )
    (net (code "39") (name "/SPI1_MOSI") (class "Default")
      (node (ref "IPS1") (pin "3") (pinfunction "1_3") (pintype "passive"))
      (node (ref "U2") (pin "28") (pinfunction "PB15_28") (pintype "passive"))
    )
    (net (code "40") (name "/SPI1_NSS") (class "Default")
      (node (ref "IPS1") (pin "7") (pinfunction "1_7") (pintype "passive"))
      (node (ref "U2") (pin "25") (pinfunction "PB12_25") (pintype "passive"))
    )
    (net (code "41") (name "/SPI1_SCK") (class "Default")
      (node (ref "IPS1") (pin "4") (pinfunction "1_4") (pintype "passive"))
      (node (ref "U2") (pin "26") (pinfunction "PB13_26") (pintype "passive"))
    )
    (net (code "42") (name "/SWCLK") (class "Default")
      (node (ref "P1") (pin "6") (pinfunction "6_6") (pintype "passive"))
      (node (ref "U2") (pin "37") (pinfunction "SWCLK_37") (pintype "passive"))
    )
    (net (code "43") (name "/SWIO") (class "Default")
      (node (ref "P1") (pin "4") (pinfunction "4_4") (pintype "passive"))
      (node (ref "U2") (pin "34") (pinfunction "SWIO_34") (pintype "passive"))
    )
    (net (code "44") (name "3.3V") (class "Default")
      (node (ref "C17") (pin "1") (pinfunction "1_1") (pintype "passive"))
      (node (ref "C18") (pin "1") (pinfunction "1_1") (pintype "passive"))
      (node (ref "C2") (pin "2") (pinfunction "2_2") (pintype "passive"))
      (node (ref "C3") (pin "2") (pinfunction "2_2") (pintype "passive"))
      (node (ref "C37") (pin "2") (pinfunction "2_2") (pintype "passive"))
      (node (ref "C4") (pin "2") (pinfunction "2_2") (pintype "passive"))
      (node (ref "C40") (pin "2") (pinfunction "2_2") (pintype "passive"))
      (node (ref "C5") (pin "2") (pinfunction "2_2") (pintype "passive"))
      (node (ref "R13") (pin "1") (pinfunction "1_1") (pintype "passive"))
      (node (ref "R14") (pin "2") (pinfunction "2_2") (pintype "passive"))
      (node (ref "R2") (pin "1") (pinfunction "1_1") (pintype "passive"))
      (node (ref "R3") (pin "1") (pinfunction "1_1") (pintype "passive"))
      (node (ref "R5") (pin "1") (pinfunction "1_1") (pintype "passive"))
      (node (ref "U2") (pin "1") (pinfunction "VBAT_1") (pintype "passive"))
      (node (ref "U2") (pin "24") (pinfunction "VDD_1_24") (pintype "passive"))
      (node (ref "U2") (pin "36") (pinfunction "VDD_2_36") (pintype "passive"))
      (node (ref "U2") (pin "48") (pinfunction "VDD_3_48") (pintype "passive"))
      (node (ref "U2") (pin "9") (pinfunction "VDDA_9") (pintype "passive"))
      (node (ref "U4") (pin "4") (pinfunction "VDD_4") (pintype "passive"))
      (node (ref "U8") (pin "2") (pinfunction "OUT_2") (pintype "passive"))
    )
    (net (code "45") (name "3.3V_ips") (class "Default")
      (node (ref "C15") (pin "2") (pinfunction "2_2") (pintype "passive"))
      (node (ref "C16") (pin "2") (pinfunction "2_2") (pintype "passive"))
      (node (ref "C24") (pin "2") (pinfunction "2_2") (pintype "passive"))
      (node (ref "C25") (pin "2") (pinfunction "2_2") (pintype "passive"))
      (node (ref "IPS1") (pin "10") (pinfunction "1_10") (pintype "passive"))
      (node (ref "IPS1") (pin "12") (pinfunction "1_12") (pintype "passive"))
      (node (ref "R11") (pin "1") (pinfunction "1_1") (pintype "passive"))
      (node (ref "R6") (pin "1") (pinfunction "1_1") (pintype "passive"))
      (node (ref "U5") (pin "2") (pinfunction "OUT_2") (pintype "passive"))
    )
    (net (code "46") (name "5V") (class "Default")
      (node (ref "C22") (pin "2") (pinfunction "2_2") (pintype "passive"))
      (node (ref "C23") (pin "2") (pinfunction "2_2") (pintype "passive"))
      (node (ref "C38") (pin "2") (pinfunction "2_2") (pintype "passive"))
      (node (ref "C39") (pin "2") (pinfunction "2_2") (pintype "passive"))
      (node (ref "D10") (pin "2") (pintype "passive"))
      (node (ref "D17") (pin "2") (pintype "passive"))
      (node (ref "D5") (pin "1") (pintype "passive"))
      (node (ref "D7") (pin "2") (pintype "passive"))
      (node (ref "P1") (pin "10") (pinfunction "10_10") (pintype "passive"))
      (node (ref "P1") (pin "9") (pinfunction "9_9") (pintype "passive"))
      (node (ref "R7") (pin "1") (pinfunction "1_1") (pintype "passive"))
      (node (ref "U1") (pin "1") (pinfunction "1_1") (pintype "passive"))
      (node (ref "U5") (pin "3") (pinfunction "IN_3") (pintype "passive"))
      (node (ref "U6") (pin "1") (pinfunction "VCC_1") (pintype "passive"))
      (node (ref "U6") (pin "3") (pinfunction "SD_3") (pintype "passive"))
      (node (ref "U7") (pin "1") (pinfunction "VCC_1") (pintype "passive"))
      (node (ref "U7") (pin "3") (pinfunction "SD_3") (pintype "passive"))
      (node (ref "U8") (pin "3") (pinfunction "IN_3") (pintype "passive"))
      (node (ref "U9") (pin "1") (pinfunction "VCC_1") (pintype "passive"))
      (node (ref "U9") (pin "3") (pinfunction "SD_3") (pintype "passive"))
    )
    (net (code "47") (name "12V") (class "Default")
      (node (ref "C12") (pin "2") (pinfunction "2_2") (pintype "passive"))
      (node (ref "C13") (pin "2") (pinfunction "2_2") (pintype "passive"))
      (node (ref "C26") (pin "2") (pinfunction "2_2") (pintype "passive"))
      (node (ref "C27") (pin "2") (pinfunction "2_2") (pintype "passive"))
      (node (ref "C28") (pin "2") (pinfunction "2_2") (pintype "passive"))
      (node (ref "D11") (pin "1") (pintype "passive"))
      (node (ref "D12") (pin "1") (pintype "passive"))
      (node (ref "D13") (pin "1") (pintype "passive"))
      (node (ref "Q2") (pin "1") (pinfunction "D_1") (pintype "passive"))
      (node (ref "Q3") (pin "1") (pinfunction "D_1") (pintype "passive"))
      (node (ref "Q4") (pin "1") (pinfunction "D_1") (pintype "passive"))
      (node (ref "S1") (pin "1") (pinfunction "1_1") (pintype "passive"))
      (node (ref "U3") (pin "4") (pinfunction "EN_4") (pintype "passive"))
      (node (ref "U3") (pin "5") (pinfunction "IN_5") (pintype "passive"))
    )
    (net (code "48") (name "GND") (class "Default")
      (node (ref "C1") (pin "2") (pinfunction "2_2") (pintype "passive"))
      (node (ref "C10") (pin "1") (pinfunction "1_1") (pintype "passive"))
      (node (ref "C12") (pin "1") (pinfunction "1_1") (pintype "passive"))
      (node (ref "C13") (pin "1") (pinfunction "1_1") (pintype "passive"))
      (node (ref "C14") (pin "1") (pinfunction "1_1") (pintype "passive"))
      (node (ref "C15") (pin "1") (pinfunction "1_1") (pintype "passive"))
      (node (ref "C16") (pin "1") (pinfunction "1_1") (pintype "passive"))
      (node (ref "C17") (pin "2") (pinfunction "2_2") (pintype "passive"))
      (node (ref "C18") (pin "2") (pinfunction "2_2") (pintype "passive"))
      (node (ref "C19") (pin "2") (pinfunction "2_2") (pintype "passive"))
      (node (ref "C2") (pin "1") (pinfunction "1_1") (pintype "passive"))
      (node (ref "C20") (pin "1") (pinfunction "1_1") (pintype "passive"))
      (node (ref "C22") (pin "1") (pinfunction "1_1") (pintype "passive"))
      (node (ref "C23") (pin "1") (pinfunction "1_1") (pintype "passive"))
      (node (ref "C24") (pin "1") (pinfunction "1_1") (pintype "passive"))
      (node (ref "C25") (pin "1") (pinfunction "1_1") (pintype "passive"))
      (node (ref "C3") (pin "1") (pinfunction "1_1") (pintype "passive"))
      (node (ref "C37") (pin "1") (pinfunction "1_1") (pintype "passive"))
      (node (ref "C38") (pin "1") (pinfunction "1_1") (pintype "passive"))
      (node (ref "C39") (pin "1") (pinfunction "1_1") (pintype "passive"))
      (node (ref "C4") (pin "1") (pinfunction "1_1") (pintype "passive"))
      (node (ref "C40") (pin "1") (pinfunction "1_1") (pintype "passive"))
      (node (ref "C5") (pin "1") (pinfunction "1_1") (pintype "passive"))
      (node (ref "C6") (pin "2") (pinfunction "2_2") (pintype "passive"))
      (node (ref "C8") (pin "2") (pinfunction "2_2") (pintype "passive"))
      (node (ref "C9") (pin "1") (pinfunction "1_1") (pintype "passive"))
      (node (ref "D2") (pin "N") (pinfunction "2_N") (pintype "passive"))
      (node (ref "D3") (pin "N") (pinfunction "2_N") (pintype "passive"))
      (node (ref "D4") (pin "N") (pinfunction "2_N") (pintype "passive"))
      (node (ref "D6") (pin "A") (pinfunction "1_A") (pintype "passive"))
      (node (ref "IPS1") (pin "13") (pinfunction "1_13") (pintype "passive"))
      (node (ref "IPS1") (pin "8") (pinfunction "1_8") (pintype "passive"))
      (node (ref "P1") (pin "1") (pinfunction "1_1") (pintype "passive"))
      (node (ref "P1") (pin "2") (pinfunction "2_2") (pintype "passive"))
      (node (ref "P2") (pin "2") (pinfunction "GND_2") (pintype "passive"))
      (node (ref "Q1") (pin "2") (pinfunction "E_2") (pintype "passive"))
      (node (ref "R1") (pin "1") (pinfunction "1_1") (pintype "passive"))
      (node (ref "R10") (pin "1") (pinfunction "1_1") (pintype "passive"))
      (node (ref "R12") (pin "2") (pinfunction "2_2") (pintype "passive"))
      (node (ref "R13") (pin "3") (pinfunction "3_3") (pintype "passive"))
      (node (ref "R15") (pin "1") (pinfunction "1_1") (pintype "passive"))
      (node (ref "R21") (pin "2") (pinfunction "2_2") (pintype "passive"))
      (node (ref "R34") (pin "2") (pinfunction "2_2") (pintype "passive"))
      (node (ref "R4") (pin "2") (pinfunction "2_2") (pintype "passive"))
      (node (ref "R44") (pin "2") (pinfunction "2_2") (pintype "passive"))
      (node (ref "R51") (pin "1") (pinfunction "1_1") (pintype "passive"))
      (node (ref "R52") (pin "1") (pinfunction "1_1") (pintype "passive"))
      (node (ref "R53") (pin "1") (pinfunction "1_1") (pintype "passive"))
      (node (ref "SW1") (pin "1") (pinfunction "1_1") (pintype "passive"))
      (node (ref "U1") (pin "4") (pinfunction "4_4") (pintype "passive"))
      (node (ref "U2") (pin "23") (pinfunction "VSS_1_23") (pintype "passive"))
      (node (ref "U2") (pin "35") (pinfunction "VSS_2_35") (pintype "passive"))
      (node (ref "U2") (pin "47") (pinfunction "VSS_3_47") (pintype "passive"))
      (node (ref "U2") (pin "8") (pinfunction "VSSA_8") (pintype "passive"))
      (node (ref "U3") (pin "2") (pinfunction "GND_2") (pintype "passive"))
      (node (ref "U4") (pin "11") (pinfunction "VSS_11") (pintype "passive"))
      (node (ref "U5") (pin "1") (pinfunction "GND_1") (pintype "passive"))
      (node (ref "U6") (pin "4") (pinfunction "GND_4") (pintype "passive"))
      (node (ref "U7") (pin "4") (pinfunction "GND_4") (pintype "passive"))
      (node (ref "U8") (pin "1") (pinfunction "GND_1") (pintype "passive"))
      (node (ref "U9") (pin "4") (pinfunction "GND_4") (pintype "passive"))
      (node (ref "X1") (pin "2") (pinfunction "GND_2") (pintype "passive"))
      (node (ref "X1") (pin "4") (pinfunction "GND_4") (pintype "passive"))
    )
    (net (code "49") (name "Net-(C10-Pad2)") (class "Default")
      (node (ref "C10") (pin "2") (pinfunction "2_2") (pintype "passive"))
      (node (ref "C11") (pin "2") (pinfunction "2_2") (pintype "passive"))
      (node (ref "C9") (pin "2") (pinfunction "2_2") (pintype "passive"))
      (node (ref "D5") (pin "2") (pintype "passive"))
      (node (ref "L1") (pin "1") (pinfunction "1_1") (pintype "passive"))
      (node (ref "R8") (pin "2") (pinfunction "2_2") (pintype "passive"))
    )
    (net (code "50") (name "Net-(C26-Pad1)") (class "Default")
      (node (ref "C26") (pin "1") (pinfunction "1_1") (pintype "passive"))
      (node (ref "R24") (pin "1") (pinfunction "1_1") (pintype "passive"))
    )
    (net (code "51") (name "Net-(C27-Pad1)") (class "Default")
      (node (ref "C27") (pin "1") (pinfunction "1_1") (pintype "passive"))
      (node (ref "R25") (pin "1") (pinfunction "1_1") (pintype "passive"))
    )
    (net (code "52") (name "Net-(C28-Pad1)") (class "Default")
      (node (ref "C28") (pin "1") (pinfunction "1_1") (pintype "passive"))
      (node (ref "R26") (pin "1") (pinfunction "1_1") (pintype "passive"))
    )
    (net (code "53") (name "Net-(C29-Pad1)") (class "Default")
      (node (ref "C29") (pin "1") (pinfunction "1_1") (pintype "passive"))
      (node (ref "R17") (pin "1") (pinfunction "1_1") (pintype "passive"))
      (node (ref "R18") (pin "2") (pinfunction "2_2") (pintype "passive"))
    )
    (net (code "54") (name "Net-(C29-Pad2)") (class "Default")
      (node (ref "C29") (pin "2") (pinfunction "2_2") (pintype "passive"))
      (node (ref "R21") (pin "1") (pinfunction "1_1") (pintype "passive"))
      (node (ref "R22") (pin "2") (pinfunction "2_2") (pintype "passive"))
    )
    (net (code "55") (name "Net-(C32-Pad1)") (class "Default")
      (node (ref "C32") (pin "1") (pinfunction "1_1") (pintype "passive"))
      (node (ref "R34") (pin "1") (pinfunction "1_1") (pintype "passive"))
      (node (ref "R35") (pin "2") (pinfunction "2_2") (pintype "passive"))
    )
    (net (code "56") (name "Net-(C32-Pad2)") (class "Default")
      (node (ref "C32") (pin "2") (pinfunction "2_2") (pintype "passive"))
      (node (ref "R27") (pin "1") (pinfunction "1_1") (pintype "passive"))
      (node (ref "R28") (pin "2") (pinfunction "2_2") (pintype "passive"))
    )
    (net (code "57") (name "Net-(C34-Pad1)") (class "Default")
      (node (ref "C34") (pin "1") (pinfunction "1_1") (pintype "passive"))
      (node (ref "R41") (pin "1") (pinfunction "1_1") (pintype "passive"))
    )
    (net (code "58") (name "Net-(C35-Pad1)") (class "Default")
      (node (ref "C35") (pin "1") (pinfunction "1_1") (pintype "passive"))
      (node (ref "R42") (pin "1") (pinfunction "1_1") (pintype "passive"))
    )
    (net (code "59") (name "Net-(C36-Pad1)") (class "Default")
      (node (ref "C36") (pin "1") (pinfunction "1_1") (pintype "passive"))
      (node (ref "R47") (pin "1") (pinfunction "1_1") (pintype "passive"))
    )
    (net (code "60") (name "Net-(C41-Pad1)") (class "Default")
      (node (ref "C41") (pin "1") (pinfunction "1_1") (pintype "passive"))
      (node (ref "R44") (pin "1") (pinfunction "1_1") (pintype "passive"))
      (node (ref "R48") (pin "2") (pinfunction "2_2") (pintype "passive"))
    )
    (net (code "61") (name "Net-(C41-Pad2)") (class "Default")
      (node (ref "C41") (pin "2") (pinfunction "2_2") (pintype "passive"))
      (node (ref "R38") (pin "1") (pinfunction "1_1") (pintype "passive"))
      (node (ref "R39") (pin "2") (pinfunction "2_2") (pintype "passive"))
    )
    (net (code "62") (name "Net-(D1-1)") (class "Default")
      (node (ref "D1") (pin "A") (pinfunction "1_A") (pintype "passive"))
      (node (ref "R2") (pin "2") (pinfunction "2_2") (pintype "passive"))
    )
    (net (code "63") (name "Net-(D2-1)") (class "Default")
      (node (ref "D2") (pin "A") (pinfunction "1_A") (pintype "passive"))
      (node (ref "R5") (pin "2") (pinfunction "2_2") (pintype "passive"))
    )
    (net (code "64") (name "Net-(D3-1)") (class "Default")
      (node (ref "D3") (pin "A") (pinfunction "1_A") (pintype "passive"))
      (node (ref "R6") (pin "2") (pinfunction "2_2") (pintype "passive"))
    )
    (net (code "65") (name "Net-(D4-1)") (class "Default")
      (node (ref "D4") (pin "A") (pinfunction "1_A") (pintype "passive"))
      (node (ref "R7") (pin "2") (pinfunction "2_2") (pintype "passive"))
    )
    (net (code "66") (name "Net-(D6-2)") (class "Default")
      (node (ref "C19") (pin "1") (pintype "passive"))
      (node (ref "D6") (pin "N") (pinfunction "2_N") (pintype "passive"))
      (node (ref "P2") (pin "1") (pinfunction "VCC_1") (pintype "passive"))
      (node (ref "S1") (pin "2") (pinfunction "2_2") (pintype "passive"))
    )
    (net (code "67") (name "Net-(IPS1-1-Pad11)") (class "Default")
      (node (ref "IPS1") (pin "11") (pinfunction "1_11") (pintype "passive"))
      (node (ref "R9") (pin "2") (pinfunction "2_2") (pintype "passive"))
    )
    (net (code "68") (name "Net-(Q1-B)") (class "Default")
      (node (ref "Q1") (pin "1") (pinfunction "B_1") (pintype "passive"))
      (node (ref "R11") (pin "2") (pinfunction "2_2") (pintype "passive"))
      (node (ref "R12") (pin "1") (pinfunction "1_1") (pintype "passive"))
    )
    (net (code "69") (name "Net-(Q1-C)") (class "Default")
      (node (ref "Q1") (pin "3") (pinfunction "C_3") (pintype "passive"))
      (node (ref "R9") (pin "1") (pinfunction "1_1") (pintype "passive"))
    )
    (net (code "70") (name "Net-(U2-PA7)") (class "Default")
      (node (ref "C14") (pin "2") (pinfunction "2_2") (pintype "passive"))
      (node (ref "R13") (pin "2") (pinfunction "2_2") (pintype "passive"))
      (node (ref "U2") (pin "17") (pinfunction "PA7_17") (pintype "passive"))
    )
    (net (code "71") (name "Net-(U3-BS)") (class "Default")
      (node (ref "C7") (pin "1") (pinfunction "1_1") (pintype "passive"))
      (node (ref "U3") (pin "1") (pinfunction "BS_1") (pintype "passive"))
    )
    (net (code "72") (name "Net-(U3-FB)") (class "Default")
      (node (ref "C11") (pin "1") (pinfunction "1_1") (pintype "passive"))
      (node (ref "R10") (pin "2") (pinfunction "2_2") (pintype "passive"))
      (node (ref "R8") (pin "1") (pinfunction "1_1") (pintype "passive"))
      (node (ref "U3") (pin "3") (pinfunction "FB_3") (pintype "passive"))
    )
    (net (code "73") (name "Net-(U3-SW)") (class "Default")
      (node (ref "C7") (pin "2") (pinfunction "2_2") (pintype "passive"))
      (node (ref "L1") (pin "2") (pinfunction "2_2") (pintype "passive"))
      (node (ref "U3") (pin "6") (pinfunction "SW_6") (pintype "passive"))
    )
    (net (code "74") (name "Net-(U6-HO)") (class "Default")
      (node (ref "D8") (pin "1") (pintype "passive"))
      (node (ref "R16") (pin "2") (pinfunction "2_2") (pintype "passive"))
      (node (ref "U6") (pin "7") (pinfunction "HO_7") (pintype "passive"))
    )
    (net (code "75") (name "Net-(U6-LO)") (class "Default")
      (node (ref "D9") (pin "1") (pintype "passive"))
      (node (ref "R20") (pin "2") (pinfunction "2_2") (pintype "passive"))
      (node (ref "U6") (pin "5") (pinfunction "LO_5") (pintype "passive"))
    )
    (net (code "76") (name "Net-(U6-VB)") (class "Default")
      (node (ref "C21") (pin "2") (pinfunction "2_2") (pintype "passive"))
      (node (ref "D7") (pin "1") (pintype "passive"))
      (node (ref "U6") (pin "8") (pinfunction "VB_8") (pintype "passive"))
    )
    (net (code "77") (name "Net-(U7-HO)") (class "Default")
      (node (ref "D14") (pin "1") (pintype "passive"))
      (node (ref "R33") (pin "2") (pinfunction "2_2") (pintype "passive"))
      (node (ref "U7") (pin "7") (pinfunction "HO_7") (pintype "passive"))
    )
    (net (code "78") (name "Net-(U7-LO)") (class "Default")
      (node (ref "D15") (pin "1") (pintype "passive"))
      (node (ref "R37") (pin "2") (pinfunction "2_2") (pintype "passive"))
      (node (ref "U7") (pin "5") (pinfunction "LO_5") (pintype "passive"))
    )
    (net (code "79") (name "Net-(U7-VB)") (class "Default")
      (node (ref "C31") (pin "2") (pinfunction "2_2") (pintype "passive"))
      (node (ref "D10") (pin "1") (pintype "passive"))
      (node (ref "U7") (pin "8") (pinfunction "VB_8") (pintype "passive"))
    )
    (net (code "80") (name "Net-(U9-HO)") (class "Default")
      (node (ref "D20") (pin "1") (pintype "passive"))
      (node (ref "R50") (pin "2") (pinfunction "2_2") (pintype "passive"))
      (node (ref "U9") (pin "7") (pinfunction "HO_7") (pintype "passive"))
    )
    (net (code "81") (name "Net-(U9-LO)") (class "Default")
      (node (ref "D21") (pin "1") (pintype "passive"))
      (node (ref "R54") (pin "2") (pinfunction "2_2") (pintype "passive"))
      (node (ref "U9") (pin "5") (pinfunction "LO_5") (pintype "passive"))
    )
    (net (code "82") (name "Net-(U9-VB)") (class "Default")
      (node (ref "C43") (pin "2") (pinfunction "2_2") (pintype "passive"))
      (node (ref "D17") (pin "1") (pintype "passive"))
      (node (ref "U9") (pin "8") (pinfunction "VB_8") (pintype "passive"))
    )
    (net (code "83") (name "unconnected-(IPS1-1-Pad2)") (class "Default")
      (node (ref "IPS1") (pin "2") (pinfunction "1_2") (pintype "passive+no_connect"))
    )
    (net (code "84") (name "unconnected-(IPS1-1-Pad9)") (class "Default")
      (node (ref "IPS1") (pin "9") (pinfunction "1_9") (pintype "passive+no_connect"))
    )
    (net (code "85") (name "unconnected-(IPS1-Pad1)") (class "Default")
      (node (ref "IPS1") (pin "1") (pinfunction "1_1") (pintype "passive+no_connect"))
    )
    (net (code "86") (name "unconnected-(P1-Pad7)") (class "Default")
      (node (ref "P1") (pin "7") (pinfunction "7_7") (pintype "passive"))
    )
    (net (code "87") (name "unconnected-(P1-Pad8)") (class "Default")
      (node (ref "P1") (pin "8") (pinfunction "8_8") (pintype "passive"))
    )
    (net (code "88") (name "unconnected-(S1-Pad3)") (class "Default")
      (node (ref "S1") (pin "3") (pinfunction "3_3") (pintype "passive+no_connect"))
    )
    (net (code "89") (name "unconnected-(U1-Pad5)") (class "Default")
      (node (ref "U1") (pin "5") (pinfunction "5_5") (pintype "passive"))
    )
    (net (code "90") (name "unconnected-(U1-Pad6)") (class "Default")
      (node (ref "U1") (pin "6") (pinfunction "6_6") (pintype "passive"))
    )
    (net (code "91") (name "unconnected-(U2-PA3-Pad13)") (class "Default")
      (node (ref "U2") (pin "13") (pinfunction "PA3_13") (pintype "passive"))
    )
    (net (code "92") (name "unconnected-(U2-PA11-Pad32)") (class "Default")
      (node (ref "U2") (pin "32") (pinfunction "PA11_32") (pintype "passive"))
    )
    (net (code "93") (name "unconnected-(U2-PA12-Pad33)") (class "Default")
      (node (ref "U2") (pin "33") (pinfunction "PA12_33") (pintype "passive"))
    )
    (net (code "94") (name "unconnected-(U2-PA15-Pad38)") (class "Default")
      (node (ref "U2") (pin "38") (pinfunction "PA15_38") (pintype "passive"))
    )
    (net (code "95") (name "unconnected-(U2-PB0-Pad18)") (class "Default")
      (node (ref "U2") (pin "18") (pinfunction "PB0_18") (pintype "passive"))
    )
    (net (code "96") (name "unconnected-(U2-PB1-Pad19)") (class "Default")
      (node (ref "U2") (pin "19") (pinfunction "PB1_19") (pintype "passive"))
    )
    (net (code "97") (name "unconnected-(U2-PB3-Pad39)") (class "Default")
      (node (ref "U2") (pin "39") (pinfunction "PB3_39") (pintype "passive"))
    )
    (net (code "98") (name "unconnected-(U2-PB4-Pad40)") (class "Default")
      (node (ref "U2") (pin "40") (pinfunction "PB4_40") (pintype "passive"))
    )
    (net (code "99") (name "unconnected-(U2-PB6-Pad42)") (class "Default")
      (node (ref "U2") (pin "42") (pinfunction "PB6_42") (pintype "passive"))
    )
    (net (code "100") (name "unconnected-(U2-PB7-Pad43)") (class "Default")
      (node (ref "U2") (pin "43") (pinfunction "PB7_43") (pintype "passive"))
    )
    (net (code "101") (name "unconnected-(U2-PB8-Pad45)") (class "Default")
      (node (ref "U2") (pin "45") (pinfunction "PB8_45") (pintype "passive"))
    )
    (net (code "102") (name "unconnected-(U2-PB9-Pad46)") (class "Default")
      (node (ref "U2") (pin "46") (pinfunction "PB9_46") (pintype "passive"))
    )
    (net (code "103") (name "unconnected-(U2-PC13-Pad2)") (class "Default")
      (node (ref "U2") (pin "2") (pinfunction "PC13_2") (pintype "passive"))
    )
    (net (code "104") (name "unconnected-(U2-PC14-Pad3)") (class "Default")
      (node (ref "U2") (pin "3") (pinfunction "PC14_3") (pintype "passive"))
    )
    (net (code "105") (name "unconnected-(U2-PC15-Pad4)") (class "Default")
      (node (ref "U2") (pin "4") (pinfunction "PC15_4") (pintype "passive"))
    )
    (net (code "106") (name "unconnected-(U5-NC-Pad4)") (class "Default")
      (node (ref "U5") (pin "4") (pinfunction "NC_4") (pintype "passive"))
    )
    (net (code "107") (name "unconnected-(U8-NC-Pad4)") (class "Default")
      (node (ref "U8") (pin "4") (pinfunction "NC_4") (pintype "passive"))
    )
  )
)
